# 3-11.net
KiCad netlist of a schematic drawn in Altium Designer
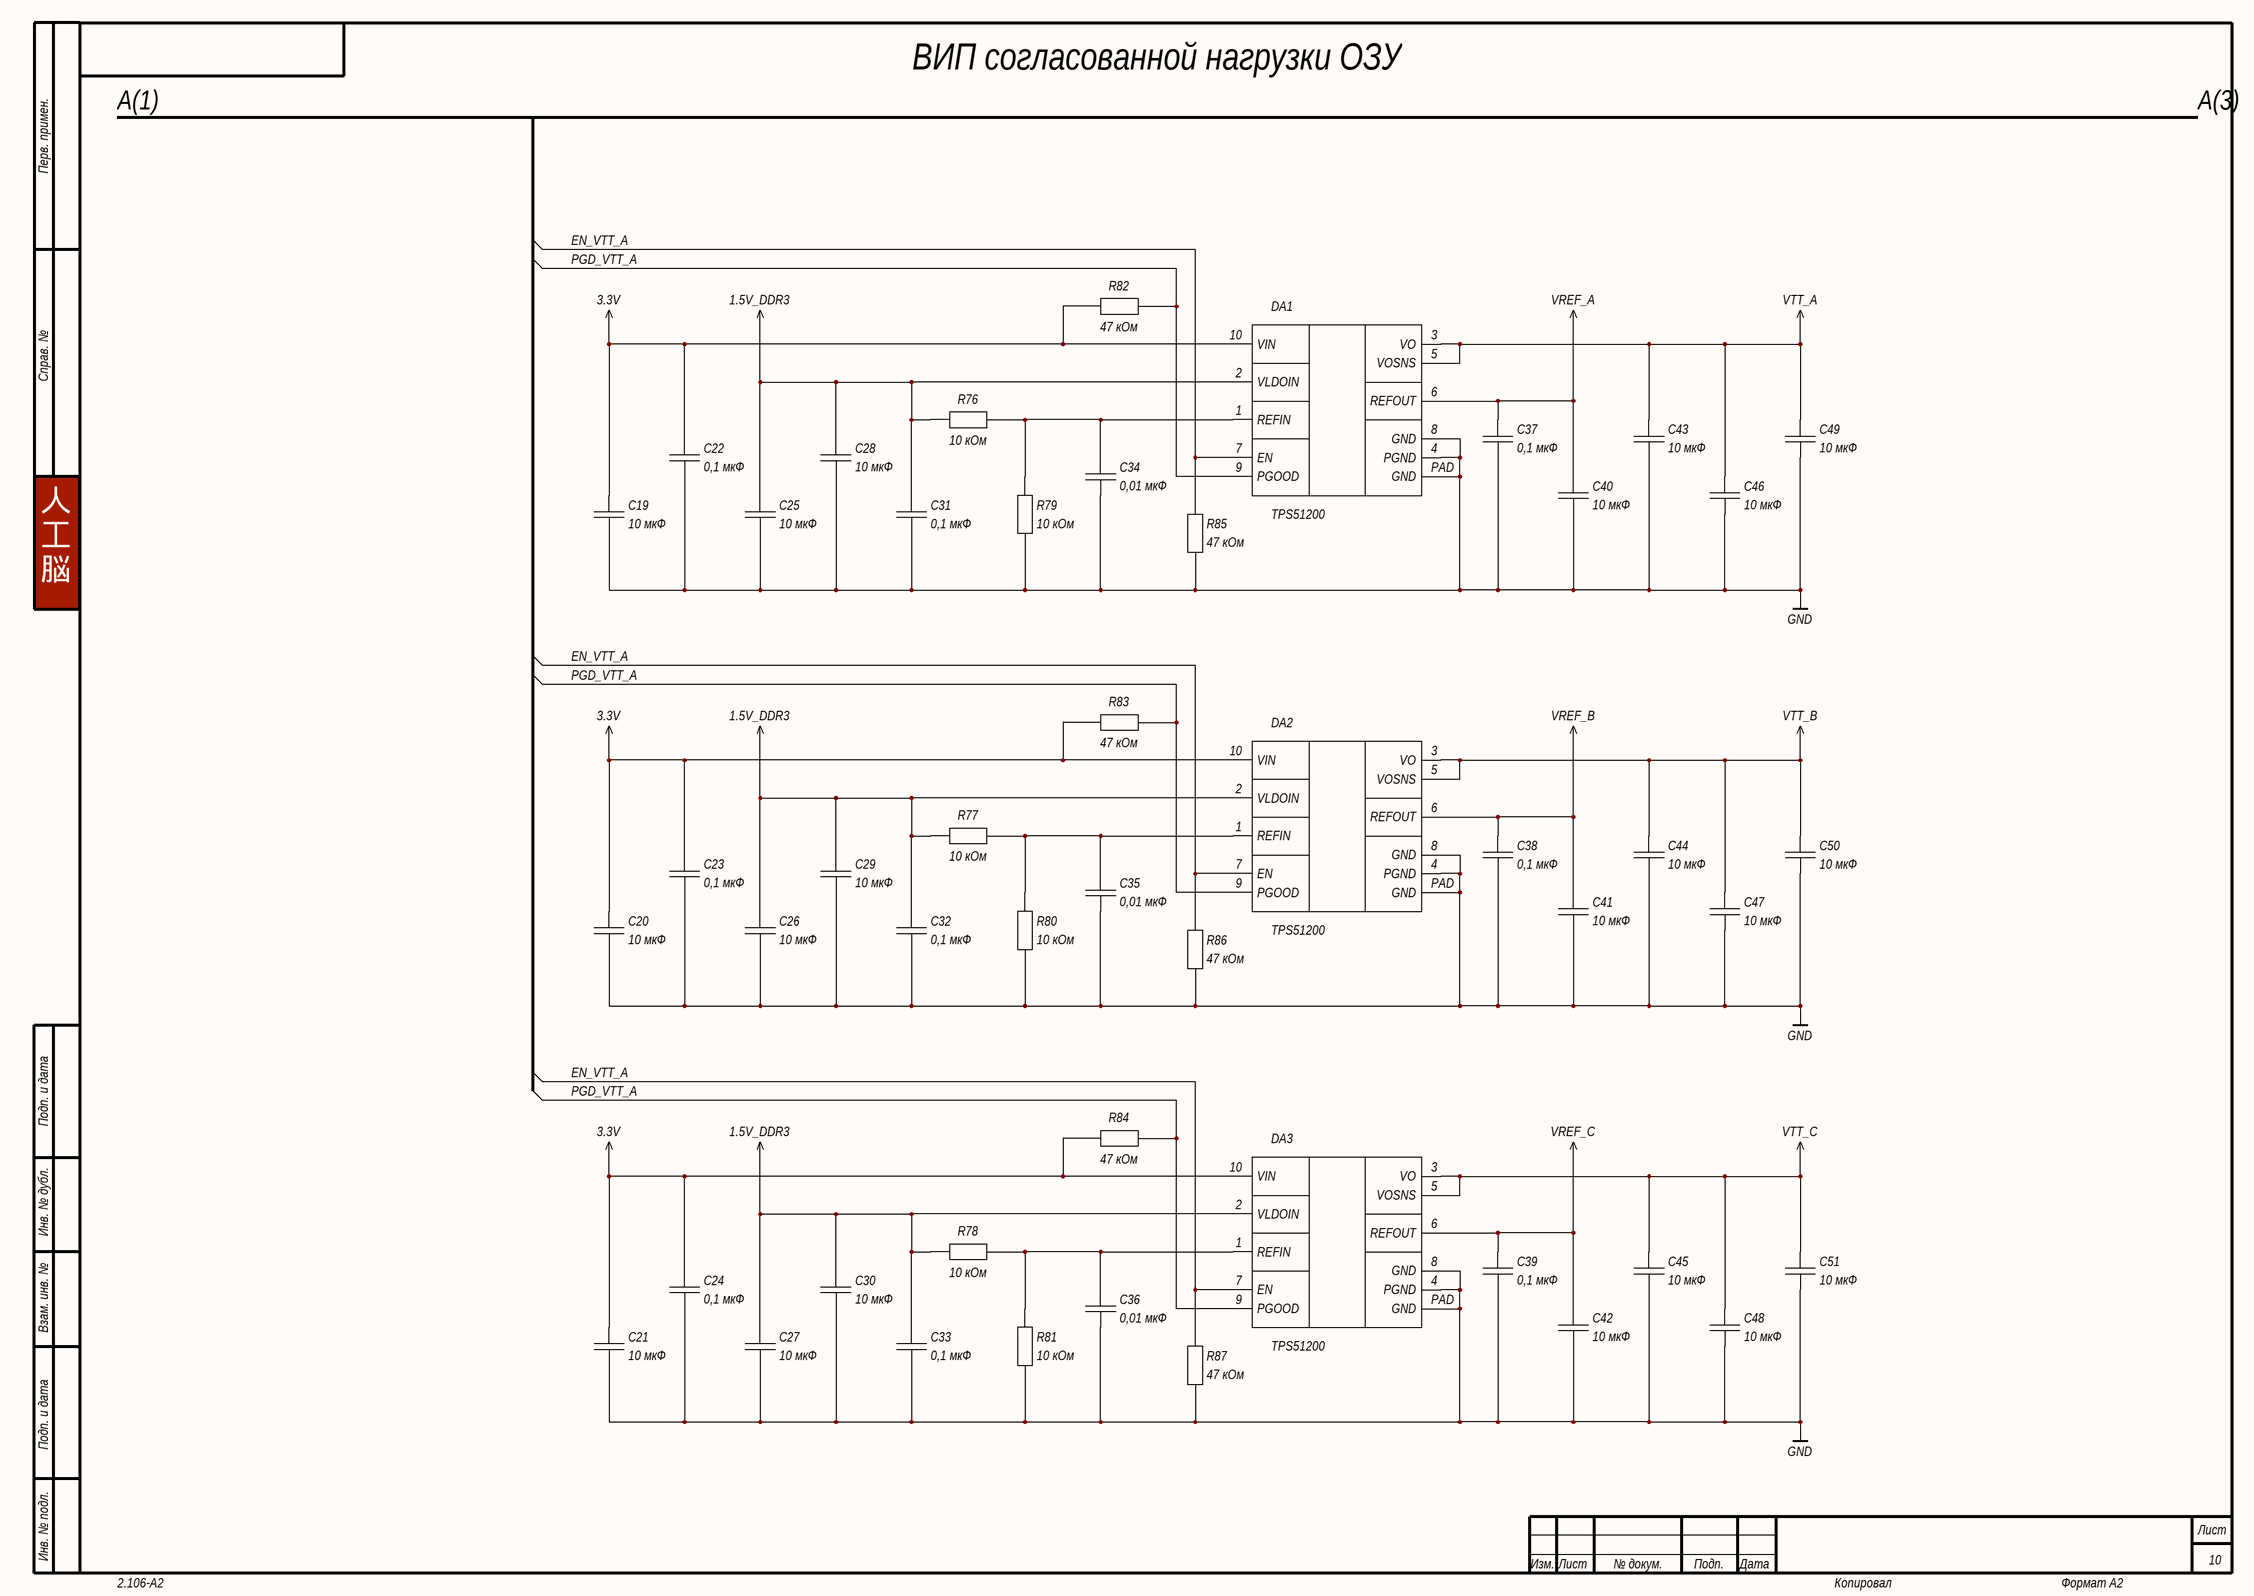
[diagram p0: Э3-11.SchDoc]

(export (version "E")
  (design (tool "Eeschema 10.0.6"))
  (components
    (comp (ref "C19")
      (value "10 мкФ")
      (footprint "C0805-B-1.25mm-NO")
      (description "0603 10 мкФ ±10% 10 В X5R")
      (fields (field (name "Comment") "1"))
      (libsource (lib "Capacitors") (part "Non Polar Ver."))
    )
    (comp (ref "C20")
      (value "10 мкФ")
      (footprint "C0805-B-1.25mm-NO")
      (description "0603 10 мкФ ±10% 10 В X5R")
      (fields (field (name "Comment") "1"))
      (libsource (lib "Capacitors") (part "Non Polar Ver."))
    )
    (comp (ref "C21")
      (value "10 мкФ")
      (footprint "C0805-B-1.25mm-NO")
      (description "0603 10 мкФ ±10% 10 В X5R")
      (fields (field (name "Comment") "1"))
      (libsource (lib "Capacitors") (part "Non Polar Ver."))
    )
    (comp (ref "C22")
      (value "0,1 мкФ")
      (footprint "C0402-B-0.5mm-NO")
      (description "0402 0,1 мкФ ±10% 25 В X7R")
      (fields (field (name "Comment") "1"))
      (libsource (lib "Capacitors") (part "Non Polar Ver."))
    )
    (comp (ref "C23")
      (value "0,1 мкФ")
      (footprint "C0402-B-0.5mm-NO")
      (description "0402 0,1 мкФ ±10% 25 В X7R")
      (fields (field (name "Comment") "1"))
      (libsource (lib "Capacitors") (part "Non Polar Ver."))
    )
    (comp (ref "C24")
      (value "0,1 мкФ")
      (footprint "C0402-B-0.5mm-NO")
      (description "0402 0,1 мкФ ±10% 25 В X7R")
      (fields (field (name "Comment") "1"))
      (libsource (lib "Capacitors") (part "Non Polar Ver."))
    )
    (comp (ref "C25")
      (value "10 мкФ")
      (footprint "C0805-B-1.25mm-NO")
      (description "0603 10 мкФ ±10% 10 В X5R")
      (fields (field (name "Comment") "1"))
      (libsource (lib "Capacitors") (part "Non Polar Ver."))
    )
    (comp (ref "C26")
      (value "10 мкФ")
      (footprint "C0805-B-1.25mm-NO")
      (description "0603 10 мкФ ±10% 10 В X5R")
      (fields (field (name "Comment") "1"))
      (libsource (lib "Capacitors") (part "Non Polar Ver."))
    )
    (comp (ref "C27")
      (value "10 мкФ")
      (footprint "C0805-B-1.25mm-NO")
      (description "0603 10 мкФ ±10% 10 В X5R")
      (fields (field (name "Comment") "1"))
      (libsource (lib "Capacitors") (part "Non Polar Ver."))
    )
    (comp (ref "C28")
      (value "10 мкФ")
      (footprint "C0805-B-1.25mm-NO")
      (description "0603 10 мкФ ±10% 10 В X5R")
      (fields (field (name "Comment") "1"))
      (libsource (lib "Capacitors") (part "Non Polar Ver."))
    )
    (comp (ref "C29")
      (value "10 мкФ")
      (footprint "C0805-B-1.25mm-NO")
      (description "0603 10 мкФ ±10% 10 В X5R")
      (fields (field (name "Comment") "1"))
      (libsource (lib "Capacitors") (part "Non Polar Ver."))
    )
    (comp (ref "C30")
      (value "10 мкФ")
      (footprint "C0805-B-1.25mm-NO")
      (description "0603 10 мкФ ±10% 10 В X5R")
      (fields (field (name "Comment") "1"))
      (libsource (lib "Capacitors") (part "Non Polar Ver."))
    )
    (comp (ref "C31")
      (value "0,1 мкФ")
      (footprint "C0402-B-0.5mm-NO")
      (description "0402 0,1 мкФ ±10% 25 В X7R")
      (fields (field (name "Comment") "1"))
      (libsource (lib "Capacitors") (part "Non Polar Ver."))
    )
    (comp (ref "C32")
      (value "0,1 мкФ")
      (footprint "C0402-B-0.5mm-NO")
      (description "0402 0,1 мкФ ±10% 25 В X7R")
      (fields (field (name "Comment") "1"))
      (libsource (lib "Capacitors") (part "Non Polar Ver."))
    )
    (comp (ref "C33")
      (value "0,1 мкФ")
      (footprint "C0402-B-0.5mm-NO")
      (description "0402 0,1 мкФ ±10% 25 В X7R")
      (fields (field (name "Comment") "1"))
      (libsource (lib "Capacitors") (part "Non Polar Ver."))
    )
    (comp (ref "C34")
      (value "0,01 мкФ")
      (footprint "C0402-B-0.5mm-NO")
      (description "0402 0,01 мкФ ±10% 25 В X7R")
      (fields (field (name "Comment") "1"))
      (libsource (lib "Capacitors") (part "Non Polar Ver."))
    )
    (comp (ref "C35")
      (value "0,01 мкФ")
      (footprint "C0402-B-0.5mm-NO")
      (description "0402 0,01 мкФ ±10% 25 В X7R")
      (fields (field (name "Comment") "1"))
      (libsource (lib "Capacitors") (part "Non Polar Ver."))
    )
    (comp (ref "C36")
      (value "0,01 мкФ")
      (footprint "C0402-B-0.5mm-NO")
      (description "0402 0,01 мкФ ±10% 25 В X7R")
      (fields (field (name "Comment") "1"))
      (libsource (lib "Capacitors") (part "Non Polar Ver."))
    )
    (comp (ref "C37")
      (value "0,1 мкФ")
      (footprint "C0402-B-0.5mm-NO")
      (description "0402 0,1 мкФ ±10% 25 В X7R")
      (fields (field (name "Comment") "1"))
      (libsource (lib "Capacitors") (part "Non Polar Ver."))
    )
    (comp (ref "C38")
      (value "0,1 мкФ")
      (footprint "C0402-B-0.5mm-NO")
      (description "0402 0,1 мкФ ±10% 25 В X7R")
      (fields (field (name "Comment") "1"))
      (libsource (lib "Capacitors") (part "Non Polar Ver."))
    )
    (comp (ref "C39")
      (value "0,1 мкФ")
      (footprint "C0402-B-0.5mm-NO")
      (description "0402 0,1 мкФ ±10% 25 В X7R")
      (fields (field (name "Comment") "1"))
      (libsource (lib "Capacitors") (part "Non Polar Ver."))
    )
    (comp (ref "C40")
      (value "10 мкФ")
      (footprint "C0805-B-1.25mm-NO")
      (description "0603 10 мкФ ±10% 10 В X5R")
      (fields (field (name "Comment") "1"))
      (libsource (lib "Capacitors") (part "Non Polar Ver."))
    )
    (comp (ref "C41")
      (value "10 мкФ")
      (footprint "C0805-B-1.25mm-NO")
      (description "0603 10 мкФ ±10% 10 В X5R")
      (fields (field (name "Comment") "1"))
      (libsource (lib "Capacitors") (part "Non Polar Ver."))
    )
    (comp (ref "C42")
      (value "10 мкФ")
      (footprint "C0805-B-1.25mm-NO")
      (description "0603 10 мкФ ±10% 10 В X5R")
      (fields (field (name "Comment") "1"))
      (libsource (lib "Capacitors") (part "Non Polar Ver."))
    )
    (comp (ref "C43")
      (value "10 мкФ")
      (footprint "C0805-B-1.25mm-NO")
      (description "0603 10 мкФ ±10% 10 В X5R")
      (fields (field (name "Comment") "1"))
      (libsource (lib "Capacitors") (part "Non Polar Ver."))
    )
    (comp (ref "C44")
      (value "10 мкФ")
      (footprint "C0805-B-1.25mm-NO")
      (description "0603 10 мкФ ±10% 10 В X5R")
      (fields (field (name "Comment") "1"))
      (libsource (lib "Capacitors") (part "Non Polar Ver."))
    )
    (comp (ref "C45")
      (value "10 мкФ")
      (footprint "C0805-B-1.25mm-NO")
      (description "0603 10 мкФ ±10% 10 В X5R")
      (fields (field (name "Comment") "1"))
      (libsource (lib "Capacitors") (part "Non Polar Ver."))
    )
    (comp (ref "C46")
      (value "10 мкФ")
      (footprint "C0805-B-1.25mm-NO")
      (description "0603 10 мкФ ±10% 10 В X5R")
      (fields (field (name "Comment") "1"))
      (libsource (lib "Capacitors") (part "Non Polar Ver."))
    )
    (comp (ref "C47")
      (value "10 мкФ")
      (footprint "C0805-B-1.25mm-NO")
      (description "0603 10 мкФ ±10% 10 В X5R")
      (fields (field (name "Comment") "1"))
      (libsource (lib "Capacitors") (part "Non Polar Ver."))
    )
    (comp (ref "C48")
      (value "10 мкФ")
      (footprint "C0805-B-1.25mm-NO")
      (description "0603 10 мкФ ±10% 10 В X5R")
      (fields (field (name "Comment") "1"))
      (libsource (lib "Capacitors") (part "Non Polar Ver."))
    )
    (comp (ref "C49")
      (value "10 мкФ")
      (footprint "C0805-B-1.25mm-NO")
      (description "0603 10 мкФ ±10% 10 В X5R")
      (fields (field (name "Comment") "1"))
      (libsource (lib "Capacitors") (part "Non Polar Ver."))
    )
    (comp (ref "C50")
      (value "10 мкФ")
      (footprint "C0805-B-1.25mm-NO")
      (description "0603 10 мкФ ±10% 10 В X5R")
      (fields (field (name "Comment") "1"))
      (libsource (lib "Capacitors") (part "Non Polar Ver."))
    )
    (comp (ref "C51")
      (value "10 мкФ")
      (footprint "C0805-B-1.25mm-NO")
      (description "0603 10 мкФ ±10% 10 В X5R")
      (fields (field (name "Comment") "1"))
      (libsource (lib "Capacitors") (part "Non Polar Ver."))
    )
    (comp (ref "DA1")
      (value "1")
      (description "Sink and Source DDR Termination Regulator")
      (fields (field (name "MANUFACTURER") "Texas Instruments, Inc.") (field (name "PARTNUMBER") "TPS51200"))
      (libsource (lib "Power") (part "TPS51200"))
    )
    (comp (ref "DA2")
      (value "1")
      (description "Sink and Source DDR Termination Regulator")
      (fields (field (name "MANUFACTURER") "Texas Instruments, Inc.") (field (name "PARTNUMBER") "TPS51200"))
      (libsource (lib "Power") (part "TPS51200"))
    )
    (comp (ref "DA3")
      (value "1")
      (description "Sink and Source DDR Termination Regulator")
      (fields (field (name "MANUFACTURER") "Texas Instruments, Inc.") (field (name "PARTNUMBER") "TPS51200"))
      (libsource (lib "Power") (part "TPS51200"))
    )
    (comp (ref "R76")
      (value "10 кОм")
      (footprint "CR0402-B-0.35mm-NO")
      (description "0402 10 кОм ±1%")
      (fields (field (name "Comment") "1"))
      (libsource (lib "Resistors") (part "Resistor Hor."))
    )
    (comp (ref "R77")
      (value "10 кОм")
      (footprint "CR0402-B-0.35mm-NO")
      (description "0402 10 кОм ±1%")
      (fields (field (name "Comment") "1"))
      (libsource (lib "Resistors") (part "Resistor Hor."))
    )
    (comp (ref "R78")
      (value "10 кОм")
      (footprint "CR0402-B-0.35mm-NO")
      (description "0402 10 кОм ±1%")
      (fields (field (name "Comment") "1"))
      (libsource (lib "Resistors") (part "Resistor Hor."))
    )
    (comp (ref "R79")
      (value "10 кОм")
      (footprint "CR0402-B-0.35mm-NO")
      (description "0402 10 кОм ±1%")
      (fields (field (name "Comment") "1"))
      (libsource (lib "Resistors") (part "Resistor Ver."))
    )
    (comp (ref "R80")
      (value "10 кОм")
      (footprint "CR0402-B-0.35mm-NO")
      (description "0402 10 кОм ±1%")
      (fields (field (name "Comment") "1"))
      (libsource (lib "Resistors") (part "Resistor Ver."))
    )
    (comp (ref "R81")
      (value "10 кОм")
      (footprint "CR0402-B-0.35mm-NO")
      (description "0402 10 кОм ±1%")
      (fields (field (name "Comment") "1"))
      (libsource (lib "Resistors") (part "Resistor Ver."))
    )
    (comp (ref "R82")
      (value "47 кОм")
      (footprint "CR0402-B-0.35mm-NO")
      (description "0402 47 кОм ±5%")
      (fields (field (name "Comment") "1"))
      (libsource (lib "Resistors") (part "Resistor Hor."))
    )
    (comp (ref "R83")
      (value "47 кОм")
      (footprint "CR0402-B-0.35mm-NO")
      (description "0402 47 кОм ±5%")
      (fields (field (name "Comment") "1"))
      (libsource (lib "Resistors") (part "Resistor Hor."))
    )
    (comp (ref "R84")
      (value "47 кОм")
      (footprint "CR0402-B-0.35mm-NO")
      (description "0402 47 кОм ±5%")
      (fields (field (name "Comment") "1"))
      (libsource (lib "Resistors") (part "Resistor Hor."))
    )
    (comp (ref "R85")
      (value "47 кОм")
      (footprint "CR0402-B-0.35mm-NO")
      (description "0402 47 кОм ±5%")
      (fields (field (name "Comment") "1"))
      (libsource (lib "Resistors") (part "Resistor Ver."))
    )
    (comp (ref "R86")
      (value "47 кОм")
      (footprint "CR0402-B-0.35mm-NO")
      (description "0402 47 кОм ±5%")
      (fields (field (name "Comment") "1"))
      (libsource (lib "Resistors") (part "Resistor Ver."))
    )
    (comp (ref "R87")
      (value "47 кОм")
      (footprint "CR0402-B-0.35mm-NO")
      (description "0402 47 кОм ±5%")
      (fields (field (name "Comment") "1"))
      (libsource (lib "Resistors") (part "Resistor Ver."))
    )
  )
  (nets
    (net (code "1") (name "/EN_VTT_A") (class "Default")
      (node (ref "DA1") (pin "7") (pinfunction "EN_7") (pintype "passive"))
      (node (ref "DA2") (pin "7") (pinfunction "EN_7") (pintype "passive"))
      (node (ref "DA3") (pin "7") (pinfunction "EN_7") (pintype "passive"))
      (node (ref "R85") (pin "1") (pinfunction "1_1") (pintype "passive"))
      (node (ref "R86") (pin "1") (pinfunction "1_1") (pintype "passive"))
      (node (ref "R87") (pin "1") (pinfunction "1_1") (pintype "passive"))
    )
    (net (code "2") (name "/PGD_VTT_A") (class "Default")
      (node (ref "DA1") (pin "9") (pinfunction "PGOOD_9") (pintype "passive"))
      (node (ref "DA2") (pin "9") (pinfunction "PGOOD_9") (pintype "passive"))
      (node (ref "DA3") (pin "9") (pinfunction "PGOOD_9") (pintype "passive"))
      (node (ref "R82") (pin "2") (pinfunction "2_2") (pintype "passive"))
      (node (ref "R83") (pin "2") (pinfunction "2_2") (pintype "passive"))
      (node (ref "R84") (pin "2") (pinfunction "2_2") (pintype "passive"))
    )
    (net (code "3") (name "1.5V_DDR3") (class "Default")
      (node (ref "C25") (pin "1") (pinfunction "1_1") (pintype "passive"))
      (node (ref "C26") (pin "1") (pinfunction "1_1") (pintype "passive"))
      (node (ref "C27") (pin "1") (pinfunction "1_1") (pintype "passive"))
      (node (ref "C28") (pin "1") (pinfunction "1_1") (pintype "passive"))
      (node (ref "C29") (pin "1") (pinfunction "1_1") (pintype "passive"))
      (node (ref "C30") (pin "1") (pinfunction "1_1") (pintype "passive"))
      (node (ref "C31") (pin "1") (pinfunction "1_1") (pintype "passive"))
      (node (ref "C32") (pin "1") (pinfunction "1_1") (pintype "passive"))
      (node (ref "C33") (pin "1") (pinfunction "1_1") (pintype "passive"))
      (node (ref "DA1") (pin "2") (pinfunction "VLDOIN_2") (pintype "passive"))
      (node (ref "DA2") (pin "2") (pinfunction "VLDOIN_2") (pintype "passive"))
      (node (ref "DA3") (pin "2") (pinfunction "VLDOIN_2") (pintype "passive"))
      (node (ref "R76") (pin "1") (pinfunction "1_1") (pintype "passive"))
      (node (ref "R77") (pin "1") (pinfunction "1_1") (pintype "passive"))
      (node (ref "R78") (pin "1") (pinfunction "1_1") (pintype "passive"))
    )
    (net (code "4") (name "3.3V") (class "Default")
      (node (ref "C19") (pin "1") (pinfunction "1_1") (pintype "passive"))
      (node (ref "C20") (pin "1") (pinfunction "1_1") (pintype "passive"))
      (node (ref "C21") (pin "1") (pinfunction "1_1") (pintype "passive"))
      (node (ref "C22") (pin "1") (pinfunction "1_1") (pintype "passive"))
      (node (ref "C23") (pin "1") (pinfunction "1_1") (pintype "passive"))
      (node (ref "C24") (pin "1") (pinfunction "1_1") (pintype "passive"))
      (node (ref "DA1") (pin "10") (pinfunction "VIN_10") (pintype "passive"))
      (node (ref "DA2") (pin "10") (pinfunction "VIN_10") (pintype "passive"))
      (node (ref "DA3") (pin "10") (pinfunction "VIN_10") (pintype "passive"))
      (node (ref "R82") (pin "1") (pinfunction "1_1") (pintype "passive"))
      (node (ref "R83") (pin "1") (pinfunction "1_1") (pintype "passive"))
      (node (ref "R84") (pin "1") (pinfunction "1_1") (pintype "passive"))
    )
    (net (code "5") (name "GND") (class "Default")
      (node (ref "C19") (pin "2") (pinfunction "2_2") (pintype "passive"))
      (node (ref "C20") (pin "2") (pinfunction "2_2") (pintype "passive"))
      (node (ref "C21") (pin "2") (pinfunction "2_2") (pintype "passive"))
      (node (ref "C22") (pin "2") (pinfunction "2_2") (pintype "passive"))
      (node (ref "C23") (pin "2") (pinfunction "2_2") (pintype "passive"))
      (node (ref "C24") (pin "2") (pinfunction "2_2") (pintype "passive"))
      (node (ref "C25") (pin "2") (pinfunction "2_2") (pintype "passive"))
      (node (ref "C26") (pin "2") (pinfunction "2_2") (pintype "passive"))
      (node (ref "C27") (pin "2") (pinfunction "2_2") (pintype "passive"))
      (node (ref "C28") (pin "2") (pinfunction "2_2") (pintype "passive"))
      (node (ref "C29") (pin "2") (pinfunction "2_2") (pintype "passive"))
      (node (ref "C30") (pin "2") (pinfunction "2_2") (pintype "passive"))
      (node (ref "C31") (pin "2") (pinfunction "2_2") (pintype "passive"))
      (node (ref "C32") (pin "2") (pinfunction "2_2") (pintype "passive"))
      (node (ref "C33") (pin "2") (pinfunction "2_2") (pintype "passive"))
      (node (ref "C34") (pin "2") (pinfunction "2_2") (pintype "passive"))
      (node (ref "C35") (pin "2") (pinfunction "2_2") (pintype "passive"))
      (node (ref "C36") (pin "2") (pinfunction "2_2") (pintype "passive"))
      (node (ref "C37") (pin "2") (pinfunction "2_2") (pintype "passive"))
      (node (ref "C38") (pin "2") (pinfunction "2_2") (pintype "passive"))
      (node (ref "C39") (pin "2") (pinfunction "2_2") (pintype "passive"))
      (node (ref "C40") (pin "2") (pinfunction "2_2") (pintype "passive"))
      (node (ref "C41") (pin "2") (pinfunction "2_2") (pintype "passive"))
      (node (ref "C42") (pin "2") (pinfunction "2_2") (pintype "passive"))
      (node (ref "C43") (pin "2") (pinfunction "2_2") (pintype "passive"))
      (node (ref "C44") (pin "2") (pinfunction "2_2") (pintype "passive"))
      (node (ref "C45") (pin "2") (pinfunction "2_2") (pintype "passive"))
      (node (ref "C46") (pin "2") (pinfunction "2_2") (pintype "passive"))
      (node (ref "C47") (pin "2") (pinfunction "2_2") (pintype "passive"))
      (node (ref "C48") (pin "2") (pinfunction "2_2") (pintype "passive"))
      (node (ref "C49") (pin "2") (pinfunction "2_2") (pintype "passive"))
      (node (ref "C50") (pin "2") (pinfunction "2_2") (pintype "passive"))
      (node (ref "C51") (pin "2") (pinfunction "2_2") (pintype "passive"))
      (node (ref "DA1") (pin "4") (pinfunction "PGND_4") (pintype "passive"))
      (node (ref "DA1") (pin "8") (pinfunction "GND_8") (pintype "passive"))
      (node (ref "DA1") (pin "PAD") (pinfunction "GND_PAD") (pintype "passive"))
      (node (ref "DA2") (pin "4") (pinfunction "PGND_4") (pintype "passive"))
      (node (ref "DA2") (pin "8") (pinfunction "GND_8") (pintype "passive"))
      (node (ref "DA2") (pin "PAD") (pinfunction "GND_PAD") (pintype "passive"))
      (node (ref "DA3") (pin "4") (pinfunction "PGND_4") (pintype "passive"))
      (node (ref "DA3") (pin "8") (pinfunction "GND_8") (pintype "passive"))
      (node (ref "DA3") (pin "PAD") (pinfunction "GND_PAD") (pintype "passive"))
      (node (ref "R79") (pin "2") (pinfunction "2_2") (pintype "passive"))
      (node (ref "R80") (pin "2") (pinfunction "2_2") (pintype "passive"))
      (node (ref "R81") (pin "2") (pinfunction "2_2") (pintype "passive"))
      (node (ref "R85") (pin "2") (pinfunction "2_2") (pintype "passive"))
      (node (ref "R86") (pin "2") (pinfunction "2_2") (pintype "passive"))
      (node (ref "R87") (pin "2") (pinfunction "2_2") (pintype "passive"))
    )
    (net (code "6") (name "Net-(DA1-REFIN)") (class "Default")
      (node (ref "C34") (pin "1") (pinfunction "1_1") (pintype "passive"))
      (node (ref "DA1") (pin "1") (pinfunction "REFIN_1") (pintype "passive"))
      (node (ref "R76") (pin "2") (pinfunction "2_2") (pintype "passive"))
      (node (ref "R79") (pin "1") (pinfunction "1_1") (pintype "passive"))
    )
    (net (code "7") (name "Net-(DA2-REFIN)") (class "Default")
      (node (ref "C35") (pin "1") (pinfunction "1_1") (pintype "passive"))
      (node (ref "DA2") (pin "1") (pinfunction "REFIN_1") (pintype "passive"))
      (node (ref "R77") (pin "2") (pinfunction "2_2") (pintype "passive"))
      (node (ref "R80") (pin "1") (pinfunction "1_1") (pintype "passive"))
    )
    (net (code "8") (name "Net-(DA3-REFIN)") (class "Default")
      (node (ref "C36") (pin "1") (pinfunction "1_1") (pintype "passive"))
      (node (ref "DA3") (pin "1") (pinfunction "REFIN_1") (pintype "passive"))
      (node (ref "R78") (pin "2") (pinfunction "2_2") (pintype "passive"))
      (node (ref "R81") (pin "1") (pinfunction "1_1") (pintype "passive"))
    )
    (net (code "9") (name "VREF_A") (class "Default")
      (node (ref "C37") (pin "1") (pinfunction "1_1") (pintype "passive"))
      (node (ref "C40") (pin "1") (pinfunction "1_1") (pintype "passive"))
      (node (ref "DA1") (pin "6") (pinfunction "REFOUT_6") (pintype "passive"))
    )
    (net (code "10") (name "VREF_B") (class "Default")
      (node (ref "C38") (pin "1") (pinfunction "1_1") (pintype "passive"))
      (node (ref "C41") (pin "1") (pinfunction "1_1") (pintype "passive"))
      (node (ref "DA2") (pin "6") (pinfunction "REFOUT_6") (pintype "passive"))
    )
    (net (code "11") (name "VREF_C") (class "Default")
      (node (ref "C39") (pin "1") (pinfunction "1_1") (pintype "passive"))
      (node (ref "C42") (pin "1") (pinfunction "1_1") (pintype "passive"))
      (node (ref "DA3") (pin "6") (pinfunction "REFOUT_6") (pintype "passive"))
    )
    (net (code "12") (name "VTT_A") (class "Default")
      (node (ref "C43") (pin "1") (pinfunction "1_1") (pintype "passive"))
      (node (ref "C46") (pin "1") (pinfunction "1_1") (pintype "passive"))
      (node (ref "C49") (pin "1") (pinfunction "1_1") (pintype "passive"))
      (node (ref "DA1") (pin "3") (pinfunction "VO_3") (pintype "passive"))
      (node (ref "DA1") (pin "5") (pinfunction "VOSNS_5") (pintype "passive"))
    )
    (net (code "13") (name "VTT_B") (class "Default")
      (node (ref "C44") (pin "1") (pinfunction "1_1") (pintype "passive"))
      (node (ref "C47") (pin "1") (pinfunction "1_1") (pintype "passive"))
      (node (ref "C50") (pin "1") (pinfunction "1_1") (pintype "passive"))
      (node (ref "DA2") (pin "3") (pinfunction "VO_3") (pintype "passive"))
      (node (ref "DA2") (pin "5") (pinfunction "VOSNS_5") (pintype "passive"))
    )
    (net (code "14") (name "VTT_C") (class "Default")
      (node (ref "C45") (pin "1") (pinfunction "1_1") (pintype "passive"))
      (node (ref "C48") (pin "1") (pinfunction "1_1") (pintype "passive"))
      (node (ref "C51") (pin "1") (pinfunction "1_1") (pintype "passive"))
      (node (ref "DA3") (pin "3") (pinfunction "VO_3") (pintype "passive"))
      (node (ref "DA3") (pin "5") (pinfunction "VOSNS_5") (pintype "passive"))
    )
  )
)
